# 2_P1.net
KiCad netlist of a schematic drawn in Altium Designer
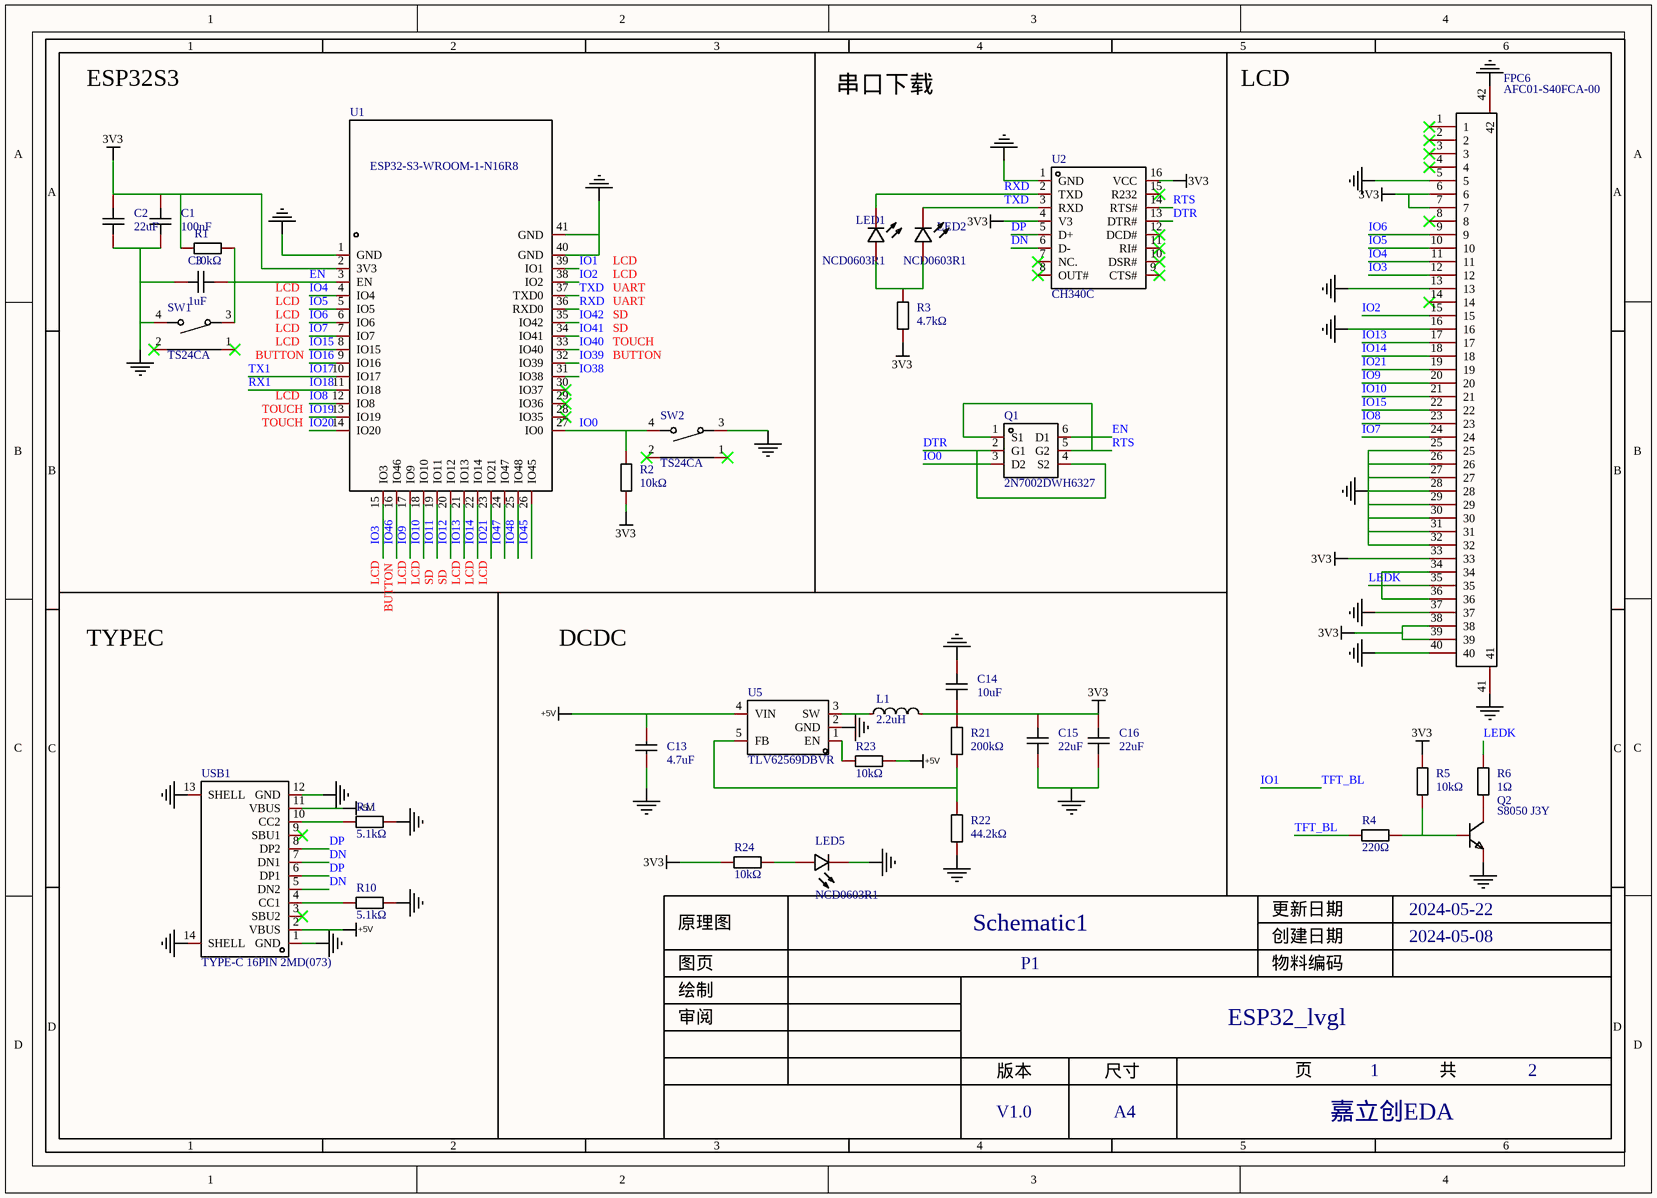
[diagram p0: 2_P1.schdoc]

(export (version "E")
  (design (tool "Eeschema 10.0.6"))
  (components
    (comp (ref "C1")
      (value "100nF")
      (description "容值:100nF;精度:±10%;额定电压:50V;材质(温度系数):X7R;")
      (fields
        (field (name "NAME") "100nF")
        (field (name "MANUFACTURER") "YAGEO(国巨)")
        (field (name "MANUFACTURER PART") "CC0603KRX7R9BB104")
      )
      (libsource (lib "altium-import") (part "root_3_CC0603KRX7R9BB104_"))
    )
    (comp (ref "C2")
      (value "22uF")
      (description "容值:22uF;精度:±20%;额定电压:10V;材质(温度系数):X5R;")
      (fields
        (field (name "NAME") "22uF")
        (field (name "MANUFACTURER") "SAMSUNG(三星)")
        (field (name "MANUFACTURER PART") "CL10A226MP8NUNE")
      )
      (libsource (lib "altium-import") (part "root_1_CL10A226MP8NUNE_"))
    )
    (comp (ref "C3")
      (value "1uF")
      (description "容值:1uF;精度:±10%;额定电压:50V;材质(温度系数):X5R;")
      (fields
        (field (name "NAME") "1uF")
        (field (name "MANUFACTURER") "SAMSUNG(三星)")
        (field (name "MANUFACTURER PART") "CL10A105KB8NNNC")
      )
      (libsource (lib "altium-import") (part "root_2_CL10A105KB8NNNC_"))
    )
    (comp (ref "C13")
      (value "4.7uF")
      (description "容值:4.7uF;精度:±10%;额定电压:25V;材质(温度系数):X5R;")
      (fields
        (field (name "NAME") "4.7uF")
        (field (name "MANUFACTURER") "SAMSUNG(三星)")
        (field (name "MANUFACTURER PART") "CL21A475KAQNNNE")
      )
      (libsource (lib "altium-import") (part "root_1_CL21A475KAQNNNE_"))
    )
    (comp (ref "C14")
      (value "10uF")
      (description "容值:10uF;精度:±20%;额定电压:6.3V;材质(温度系数):X5R;")
      (fields
        (field (name "NAME") "10uF")
        (field (name "MANUFACTURER") "SAMSUNG(三星)")
        (field (name "MANUFACTURER PART") "CL10A106MQ8NNNC")
      )
      (libsource (lib "altium-import") (part "root_1_CL10A106MQ8NNNC_"))
    )
    (comp (ref "C15")
      (value "22uF")
      (description "容值:22uF;精度:±20%;额定电压:6.3V;材质(温度系数):X5R;")
      (fields
        (field (name "NAME") "22uF")
        (field (name "MANUFACTURER") "SAMSUNG(三星)")
        (field (name "MANUFACTURER PART") "CL10A226MQ8NRNC")
      )
      (libsource (lib "altium-import") (part "root_1_CL10A226MQ8NRNC_"))
    )
    (comp (ref "C16")
      (value "22uF")
      (description "容值:22uF;精度:±20%;额定电压:6.3V;材质(温度系数):X5R;")
      (fields
        (field (name "NAME") "22uF")
        (field (name "MANUFACTURER") "SAMSUNG(三星)")
        (field (name "MANUFACTURER PART") "CL10A226MQ8NRNC")
      )
      (libsource (lib "altium-import") (part "root_1_CL10A226MQ8NRNC_"))
    )
    (comp (ref "FPC6")
      (value "AFC01-S40FCA-00")
      (description "锁定特性:翻盖式;触点类型:下接;触点数量:40P;间距:0.5mm;安装类型:卧贴;")
      (fields (field (name "NAME") "AFC01-S40FCA-00") (field (name "MANUFACTURER") "JS(钜硕电子)"))
      (libsource (lib "altium-import") (part "root_0_AFC01-S40FCA-00_"))
    )
    (comp (ref "L1")
      (value "2.2uH")
      (description "电感值:2.2uH;精度:±20%;额定电流:9.5A;饱和电流(Isat):10A;类型:一体成型电感;")
      (fields
        (field (name "NAME") "2.2uH")
        (field (name "MANUFACTURER") "cjiang(长江微电)")
        (field (name "MANUFACTURER PART") "FXL0630-2R2-M")
      )
      (libsource (lib "altium-import") (part "root_0_FXL0630-2R2-M_"))
    )
    (comp (ref "LED1")
      (value "NCD0603R1")
      (fields (field (name "NAME") "NCD0603R1") (field (name "MANUFACTURER") "国星光电"))
      (libsource (lib "altium-import") (part "root_3_NCD0603R1_C84263_"))
    )
    (comp (ref "LED2")
      (value "NCD0603R1")
      (fields (field (name "NAME") "NCD0603R1") (field (name "MANUFACTURER") "国星光电"))
      (libsource (lib "altium-import") (part "root_3_NCD0603R1_C84263_"))
    )
    (comp (ref "LED5")
      (value "NCD0603R1")
      (fields (field (name "NAME") "NCD0603R1") (field (name "MANUFACTURER") "国星光电"))
      (libsource (lib "altium-import") (part "root_2_NCD0603R1_C84263_"))
    )
    (comp (ref "Q1")
      (value "2N7002DWH6327")
      (fields (field (name "NAME") "2N7002DWH6327") (field (name "MANUFACTURER") "Infineon(英飞凌)"))
      (libsource (lib "altium-import") (part "root_0_2N7002DWH6327_"))
    )
    (comp (ref "Q2")
      (value "S8050 J3Y")
      (description "晶体管类型:NPN;集电极电流(Ic):500mA;集射极击穿电压(Vceo):25V;功率(Pd):300mW;直流电流增益(hFE@Ic,Vce):200@50mA,1V;")
      (fields (field (name "NAME") "S8050 J3Y") (field (name "MANUFACTURER") "CJ(江苏长电/长晶)"))
      (libsource (lib "altium-import") (part "root_0_S8050 J3Y_C2146_"))
    )
    (comp (ref "R1")
      (value "10kΩ")
      (description "电阻类型:厚膜电阻;阻值:10kΩ;精度:±1%;功率:100mW;最大工作电压:75V;温度系数:±100ppm/℃;")
      (fields
        (field (name "NAME") "10kΩ")
        (field (name "MANUFACTURER") "UNI-ROYAL(厚声)")
        (field (name "MANUFACTURER PART") "0603WAF1002T5E")
      )
      (libsource (lib "altium-import") (part "root_0_0603WAF1002T5E_"))
    )
    (comp (ref "R2")
      (value "10kΩ")
      (description "电阻类型:厚膜电阻;阻值:10kΩ;精度:±1%;功率:100mW;最大工作电压:75V;温度系数:±100ppm/℃;")
      (fields
        (field (name "NAME") "10kΩ")
        (field (name "MANUFACTURER") "UNI-ROYAL(厚声)")
        (field (name "MANUFACTURER PART") "0603WAF1002T5E")
      )
      (libsource (lib "altium-import") (part "root_1_0603WAF1002T5E_"))
    )
    (comp (ref "R3")
      (value "4.7kΩ")
      (description "电阻类型:厚膜电阻;阻值:4.7kΩ;精度:±1%;功率:100mW;最大工作电压:75V;温度系数:±100ppm/℃;")
      (fields
        (field (name "NAME") "4.7kΩ")
        (field (name "MANUFACTURER") "UNI-ROYAL(厚声)")
        (field (name "MANUFACTURER PART") "0603WAF4701T5E")
      )
      (libsource (lib "altium-import") (part "root_1_0603WAF4701T5E_"))
    )
    (comp (ref "R4")
      (value "220Ω")
      (description "电阻类型:厚膜电阻;阻值:220Ω;精度:±1%;功率:100mW;最大工作电压:75V;温度系数:±100ppm/℃;")
      (fields
        (field (name "NAME") "220Ω")
        (field (name "MANUFACTURER") "UNI-ROYAL(厚声)")
        (field (name "MANUFACTURER PART") "0603WAF2200T5E")
      )
      (libsource (lib "altium-import") (part "root_0_0603WAF2200T5E_"))
    )
    (comp (ref "R5")
      (value "10kΩ")
      (description "电阻类型:厚膜电阻;阻值:10kΩ;精度:±1%;功率:100mW;最大工作电压:75V;温度系数:±100ppm/℃;")
      (fields
        (field (name "NAME") "10kΩ")
        (field (name "MANUFACTURER") "UNI-ROYAL(厚声)")
        (field (name "MANUFACTURER PART") "0603WAF1002T5E")
      )
      (libsource (lib "altium-import") (part "root_1_0603WAF1002T5E_"))
    )
    (comp (ref "R6")
      (value "1Ω")
      (description "电阻类型:厚膜电阻;阻值:1Ω;精度:±1%;功率:100mW;最大工作电压:75V;温度系数:±400ppm/℃;")
      (fields
        (field (name "NAME") "1Ω")
        (field (name "MANUFACTURER") "UNI-ROYAL(厚声)")
        (field (name "MANUFACTURER PART") "0603WAF100KT5E")
      )
      (libsource (lib "altium-import") (part "root_1_0603WAF100KT5E_"))
    )
    (comp (ref "R10")
      (value "5.1kΩ")
      (description "电阻类型:厚膜电阻;阻值:5.1kΩ;精度:±1%;功率:100mW;最大工作电压:75V;温度系数:±100ppm/℃;")
      (fields
        (field (name "NAME") "5.1kΩ")
        (field (name "MANUFACTURER") "UNI-ROYAL(厚声)")
        (field (name "MANUFACTURER PART") "0603WAF5101T5E")
      )
      (libsource (lib "altium-import") (part "root_0_0603WAF5101T5E_"))
    )
    (comp (ref "R11")
      (value "5.1kΩ")
      (description "电阻类型:厚膜电阻;阻值:5.1kΩ;精度:±1%;功率:100mW;最大工作电压:75V;温度系数:±100ppm/℃;")
      (fields
        (field (name "NAME") "5.1kΩ")
        (field (name "MANUFACTURER") "UNI-ROYAL(厚声)")
        (field (name "MANUFACTURER PART") "0603WAF5101T5E")
      )
      (libsource (lib "altium-import") (part "root_0_0603WAF5101T5E_"))
    )
    (comp (ref "R21")
      (value "200kΩ")
      (description "电阻类型:厚膜电阻;阻值:200kΩ;精度:±1%;功率:100mW;最大工作电压:75V;温度系数:±100ppm/℃;")
      (fields
        (field (name "NAME") "200kΩ")
        (field (name "MANUFACTURER") "UNI-ROYAL(厚声)")
        (field (name "MANUFACTURER PART") "0603WAF2003T5E")
      )
      (libsource (lib "altium-import") (part "root_1_0603WAF2003T5E_"))
    )
    (comp (ref "R22")
      (value "44.2kΩ")
      (description "电阻类型:厚膜电阻;阻值:44.2kΩ;精度:±1%;功率:100mW;最大工作电压:75V;温度系数:±100ppm/℃;")
      (fields
        (field (name "NAME") "44.2kΩ")
        (field (name "MANUFACTURER") "UNI-ROYAL(厚声)")
        (field (name "MANUFACTURER PART") "0603WAF4422T5E")
      )
      (libsource (lib "altium-import") (part "root_1_0603WAF4422T5E_"))
    )
    (comp (ref "R23")
      (value "10kΩ")
      (description "电阻类型:厚膜电阻;阻值:10kΩ;精度:±1%;功率:100mW;最大工作电压:75V;温度系数:±100ppm/℃;")
      (fields
        (field (name "NAME") "10kΩ")
        (field (name "MANUFACTURER") "UNI-ROYAL(厚声)")
        (field (name "MANUFACTURER PART") "0603WAF1002T5E")
      )
      (libsource (lib "altium-import") (part "root_0_0603WAF1002T5E_"))
    )
    (comp (ref "R24")
      (value "10kΩ")
      (description "电阻类型:厚膜电阻;阻值:10kΩ;精度:±1%;功率:100mW;最大工作电压:75V;温度系数:±100ppm/℃;")
      (fields
        (field (name "NAME") "10kΩ")
        (field (name "MANUFACTURER") "UNI-ROYAL(厚声)")
        (field (name "MANUFACTURER PART") "0603WAF1002T5E")
      )
      (libsource (lib "altium-import") (part "root_0_0603WAF1002T5E_"))
    )
    (comp (ref "SW1")
      (value "TS24CA")
      (description "电路结构:单刀单掷;按钮形状:矩形按钮;安装方式:卧贴;开关长度:4.55mm;开关宽度:1.8mm;开关高度:3.5mm;触点电流:50mA;额定电压(DC):12V;带灯:-;机械寿命:-;")
      (fields (field (name "NAME") "TS24CA") (field (name "MANUFACTURER") "SHOU HAN(首韩)"))
      (libsource (lib "altium-import") (part "root_2_TS24CA_"))
    )
    (comp (ref "SW2")
      (value "TS24CA")
      (description "电路结构:单刀单掷;按钮形状:矩形按钮;安装方式:卧贴;开关长度:4.55mm;开关宽度:1.8mm;开关高度:3.5mm;触点电流:50mA;额定电压(DC):12V;带灯:-;机械寿命:-;")
      (fields (field (name "NAME") "TS24CA") (field (name "MANUFACTURER") "SHOU HAN(首韩)"))
      (libsource (lib "altium-import") (part "root_2_TS24CA_"))
    )
    (comp (ref "U1")
      (value "ESP32-S3-WROOM-1-N16R8")
      (fields (field (name "NAME") "ESP32-S3-WROOM-1-N16R8") (field (name "MANUFACTURER") "ESPRESSIF(乐鑫)"))
      (libsource (lib "altium-import") (part "root_0_ESP32-S3-WROOM-1-N16R8_"))
    )
    (comp (ref "U2")
      (value "CH340C")
      (description "应用功能:收发器;接口协议:USB 2.0;数据速率:2Mbps;")
      (fields (field (name "NAME") "CH340C") (field (name "MANUFACTURER") "WCH(南京沁恒)"))
      (libsource (lib "altium-import") (part "root_0_CH340C_"))
    )
    (comp (ref "U5")
      (value "TLV62569DBVR")
      (description "功能类型:降压型;输出类型:可调;输入电压:2.5V~5.5V;输出电压:600mV~5.5V;输出电流(最大值):2A;")
      (fields (field (name "NAME") "TLV62569DBVR") (field (name "MANUFACTURER") "TI(德州仪器)"))
      (libsource (lib "altium-import") (part "root_2_TLV62569DBVR_"))
    )
    (comp (ref "USB1")
      (value "TYPE-C 16PIN 2MD(073)")
      (description "连接器类型:Type-C;标准:-;公母:母;端口数量:1;触点数量:16P;安装方式:卧贴;额定电流 - 电源:5A;工作温度范围:-25℃~+85℃;")
      (fields (field (name "NAME") "TYPE-C 16PIN 2MD(073)") (field (name "MANUFACTURER") "SHOU HAN(首韩)"))
      (libsource (lib "altium-import") (part "root_2_TYPE-C 16PIN 2MD(073)_"))
    )
  )
  (nets
    (net (code "1") (name "+5V") (class "Default")
      (node (ref "C13") (pin "2") (pinfunction "2_2") (pintype "passive"))
      (node (ref "R23") (pin "2") (pinfunction "2_2") (pintype "passive"))
      (node (ref "U5") (pin "4") (pinfunction "VIN_4") (pintype "passive"))
      (node (ref "USB1") (pin "11") (pinfunction "VBUS_11") (pintype "passive"))
      (node (ref "USB1") (pin "2") (pinfunction "VBUS_2") (pintype "passive"))
    )
    (net (code "2") (name "/DN") (class "Default")
      (node (ref "U2") (pin "6") (pinfunction "D-_6") (pintype "passive"))
      (node (ref "USB1") (pin "5") (pinfunction "DN2_5") (pintype "passive"))
      (node (ref "USB1") (pin "7") (pinfunction "DN1_7") (pintype "passive"))
    )
    (net (code "3") (name "/DP") (class "Default")
      (node (ref "U2") (pin "5") (pinfunction "D+_5") (pintype "passive"))
      (node (ref "USB1") (pin "6") (pinfunction "DP1_6") (pintype "passive"))
      (node (ref "USB1") (pin "8") (pinfunction "DP2_8") (pintype "passive"))
    )
    (net (code "4") (name "/DTR") (class "Default")
      (node (ref "Q1") (pin "2") (pinfunction "G1_2") (pintype "passive"))
      (node (ref "Q1") (pin "4") (pinfunction "S2_4") (pintype "passive"))
      (node (ref "U2") (pin "13") (pinfunction "DTR#_13") (pintype "passive"))
    )
    (net (code "5") (name "/EN") (class "Default")
      (node (ref "C3") (pin "1") (pinfunction "1_1") (pintype "passive"))
      (node (ref "Q1") (pin "6") (pinfunction "D1_6") (pintype "passive"))
      (node (ref "R1") (pin "2") (pinfunction "2_2") (pintype "passive"))
      (node (ref "SW1") (pin "3") (pinfunction "3_3") (pintype "passive"))
      (node (ref "U1") (pin "3") (pinfunction "EN_3") (pintype "passive"))
    )
    (net (code "6") (name "/IO0") (class "Default")
      (node (ref "Q1") (pin "3") (pinfunction "D2_3") (pintype "passive"))
      (node (ref "R2") (pin "2") (pinfunction "2_2") (pintype "passive"))
      (node (ref "SW2") (pin "4") (pinfunction "4_4") (pintype "passive"))
      (node (ref "U1") (pin "27") (pinfunction "IO0_27") (pintype "passive"))
    )
    (net (code "7") (name "/IO1") (class "Default")
      (node (ref "R4") (pin "1") (pinfunction "1_1") (pintype "passive"))
      (node (ref "U1") (pin "39") (pinfunction "IO1_39") (pintype "passive"))
    )
    (net (code "8") (name "/IO2") (class "Default")
      (node (ref "FPC6") (pin "15") (pinfunction "15_15") (pintype "passive"))
      (node (ref "U1") (pin "38") (pinfunction "IO2_38") (pintype "passive"))
    )
    (net (code "9") (name "/IO3") (class "Default")
      (node (ref "FPC6") (pin "12") (pinfunction "12_12") (pintype "passive"))
      (node (ref "U1") (pin "15") (pinfunction "IO3_15") (pintype "passive"))
    )
    (net (code "10") (name "/IO4") (class "Default")
      (node (ref "FPC6") (pin "11") (pinfunction "11_11") (pintype "passive"))
      (node (ref "U1") (pin "4") (pinfunction "IO4_4") (pintype "passive"))
    )
    (net (code "11") (name "/IO5") (class "Default")
      (node (ref "FPC6") (pin "10") (pinfunction "10_10") (pintype "passive"))
      (node (ref "U1") (pin "5") (pinfunction "IO5_5") (pintype "passive"))
    )
    (net (code "12") (name "/IO6") (class "Default")
      (node (ref "FPC6") (pin "9") (pinfunction "9_9") (pintype "passive"))
      (node (ref "U1") (pin "6") (pinfunction "IO6_6") (pintype "passive"))
    )
    (net (code "13") (name "/IO7") (class "Default")
      (node (ref "FPC6") (pin "24") (pinfunction "24_24") (pintype "passive"))
      (node (ref "U1") (pin "7") (pinfunction "IO7_7") (pintype "passive"))
    )
    (net (code "14") (name "/IO8") (class "Default")
      (node (ref "FPC6") (pin "23") (pinfunction "23_23") (pintype "passive"))
      (node (ref "U1") (pin "12") (pinfunction "IO8_12") (pintype "passive"))
    )
    (net (code "15") (name "/IO9") (class "Default")
      (node (ref "FPC6") (pin "20") (pinfunction "20_20") (pintype "passive"))
      (node (ref "U1") (pin "17") (pinfunction "IO9_17") (pintype "passive"))
    )
    (net (code "16") (name "/IO10") (class "Default")
      (node (ref "FPC6") (pin "21") (pinfunction "21_21") (pintype "passive"))
      (node (ref "U1") (pin "18") (pinfunction "IO10_18") (pintype "passive"))
    )
    (net (code "17") (name "/IO11") (class "Default")
      (node (ref "U1") (pin "19") (pinfunction "IO11_19") (pintype "passive"))
    )
    (net (code "18") (name "/IO12") (class "Default")
      (node (ref "U1") (pin "20") (pinfunction "IO12_20") (pintype "passive"))
    )
    (net (code "19") (name "/IO13") (class "Default")
      (node (ref "FPC6") (pin "17") (pinfunction "17_17") (pintype "passive"))
      (node (ref "U1") (pin "21") (pinfunction "IO13_21") (pintype "passive"))
    )
    (net (code "20") (name "/IO14") (class "Default")
      (node (ref "FPC6") (pin "18") (pinfunction "18_18") (pintype "passive"))
      (node (ref "U1") (pin "22") (pinfunction "IO14_22") (pintype "passive"))
    )
    (net (code "21") (name "/IO15") (class "Default")
      (node (ref "FPC6") (pin "22") (pinfunction "22_22") (pintype "passive"))
      (node (ref "U1") (pin "8") (pinfunction "IO15_8") (pintype "passive"))
    )
    (net (code "22") (name "/IO16") (class "Default")
      (node (ref "U1") (pin "9") (pinfunction "IO16_9") (pintype "passive"))
    )
    (net (code "23") (name "/IO17") (class "Default")
      (node (ref "U1") (pin "10") (pinfunction "IO17_10") (pintype "passive"))
    )
    (net (code "24") (name "/IO18") (class "Default")
      (node (ref "U1") (pin "11") (pinfunction "IO18_11") (pintype "passive"))
    )
    (net (code "25") (name "/IO19") (class "Default")
      (node (ref "U1") (pin "13") (pinfunction "IO19_13") (pintype "passive"))
    )
    (net (code "26") (name "/IO20") (class "Default")
      (node (ref "U1") (pin "14") (pinfunction "IO20_14") (pintype "passive"))
    )
    (net (code "27") (name "/IO21") (class "Default")
      (node (ref "FPC6") (pin "19") (pinfunction "19_19") (pintype "passive"))
      (node (ref "U1") (pin "23") (pinfunction "IO21_23") (pintype "passive"))
    )
    (net (code "28") (name "/IO38") (class "Default")
      (node (ref "U1") (pin "31") (pinfunction "IO38_31") (pintype "passive"))
    )
    (net (code "29") (name "/IO39") (class "Default")
      (node (ref "U1") (pin "32") (pinfunction "IO39_32") (pintype "passive"))
    )
    (net (code "30") (name "/IO40") (class "Default")
      (node (ref "U1") (pin "33") (pinfunction "IO40_33") (pintype "passive"))
    )
    (net (code "31") (name "/IO41") (class "Default")
      (node (ref "U1") (pin "34") (pinfunction "IO41_34") (pintype "passive"))
    )
    (net (code "32") (name "/IO42") (class "Default")
      (node (ref "U1") (pin "35") (pinfunction "IO42_35") (pintype "passive"))
    )
    (net (code "33") (name "/IO45") (class "Default")
      (node (ref "U1") (pin "26") (pinfunction "IO45_26") (pintype "passive"))
    )
    (net (code "34") (name "/IO46") (class "Default")
      (node (ref "U1") (pin "16") (pinfunction "IO46_16") (pintype "passive"))
    )
    (net (code "35") (name "/IO47") (class "Default")
      (node (ref "U1") (pin "24") (pinfunction "IO47_24") (pintype "passive"))
    )
    (net (code "36") (name "/IO48") (class "Default")
      (node (ref "U1") (pin "25") (pinfunction "IO48_25") (pintype "passive"))
    )
    (net (code "37") (name "/LEDK") (class "Default")
      (node (ref "FPC6") (pin "34") (pinfunction "34_34") (pintype "passive"))
      (node (ref "FPC6") (pin "35") (pinfunction "35_35") (pintype "passive"))
      (node (ref "FPC6") (pin "36") (pinfunction "36_36") (pintype "passive"))
      (node (ref "R6") (pin "2") (pinfunction "2_2") (pintype "passive"))
    )
    (net (code "38") (name "/RTS") (class "Default")
      (node (ref "Q1") (pin "1") (pinfunction "S1_1") (pintype "passive"))
      (node (ref "Q1") (pin "5") (pinfunction "G2_5") (pintype "passive"))
      (node (ref "U2") (pin "14") (pinfunction "RTS#_14") (pintype "passive"))
    )
    (net (code "39") (name "/RXD") (class "Default")
      (node (ref "LED1") (pin "1") (pinfunction "K_1") (pintype "passive"))
      (node (ref "U1") (pin "36") (pinfunction "RXD0_36") (pintype "passive"))
      (node (ref "U2") (pin "2") (pinfunction "TXD_2") (pintype "passive"))
    )
    (net (code "40") (name "/TXD") (class "Default")
      (node (ref "LED2") (pin "1") (pinfunction "K_1") (pintype "passive"))
      (node (ref "U1") (pin "37") (pinfunction "TXD0_37") (pintype "passive"))
      (node (ref "U2") (pin "3") (pinfunction "RXD_3") (pintype "passive"))
    )
    (net (code "41") (name "3V3") (class "Default")
      (node (ref "C1") (pin "1") (pinfunction "1_1") (pintype "passive"))
      (node (ref "C14") (pin "1") (pinfunction "1_1") (pintype "passive"))
      (node (ref "C15") (pin "2") (pinfunction "2_2") (pintype "passive"))
      (node (ref "C16") (pin "2") (pinfunction "2_2") (pintype "passive"))
      (node (ref "C2") (pin "2") (pinfunction "2_2") (pintype "passive"))
      (node (ref "FPC6") (pin "33") (pinfunction "33_33") (pintype "passive"))
      (node (ref "FPC6") (pin "38") (pinfunction "38_38") (pintype "passive"))
      (node (ref "FPC6") (pin "39") (pinfunction "39_39") (pintype "passive"))
      (node (ref "FPC6") (pin "6") (pinfunction "6_6") (pintype "passive"))
      (node (ref "FPC6") (pin "7") (pinfunction "7_7") (pintype "passive"))
      (node (ref "L1") (pin "2") (pinfunction "2_2") (pintype "passive"))
      (node (ref "R1") (pin "1") (pinfunction "1_1") (pintype "passive"))
      (node (ref "R2") (pin "1") (pinfunction "1_1") (pintype "passive"))
      (node (ref "R21") (pin "2") (pinfunction "2_2") (pintype "passive"))
      (node (ref "R24") (pin "1") (pinfunction "1_1") (pintype "passive"))
      (node (ref "R3") (pin "1") (pinfunction "1_1") (pintype "passive"))
      (node (ref "R5") (pin "2") (pinfunction "2_2") (pintype "passive"))
      (node (ref "U1") (pin "2") (pinfunction "3V3_2") (pintype "passive"))
      (node (ref "U2") (pin "16") (pinfunction "VCC_16") (pintype "passive"))
      (node (ref "U2") (pin "4") (pinfunction "V3_4") (pintype "passive"))
    )
    (net (code "42") (name "<NO NET>") (class "Default")
      (node (ref "C1") (pin "2") (pinfunction "2_2") (pintype "passive"))
      (node (ref "C13") (pin "1") (pinfunction "1_1") (pintype "passive"))
      (node (ref "C14") (pin "2") (pinfunction "2_2") (pintype "passive"))
      (node (ref "C15") (pin "1") (pinfunction "1_1") (pintype "passive"))
      (node (ref "C16") (pin "1") (pinfunction "1_1") (pintype "passive"))
      (node (ref "C2") (pin "1") (pinfunction "1_1") (pintype "passive"))
      (node (ref "C3") (pin "2") (pinfunction "2_2") (pintype "passive"))
      (node (ref "FPC6") (pin "13") (pinfunction "13_13") (pintype "passive"))
      (node (ref "FPC6") (pin "16") (pinfunction "16_16") (pintype "passive"))
      (node (ref "FPC6") (pin "25") (pinfunction "25_25") (pintype "passive"))
      (node (ref "FPC6") (pin "26") (pinfunction "26_26") (pintype "passive"))
      (node (ref "FPC6") (pin "27") (pinfunction "27_27") (pintype "passive"))
      (node (ref "FPC6") (pin "28") (pinfunction "28_28") (pintype "passive"))
      (node (ref "FPC6") (pin "29") (pinfunction "29_29") (pintype "passive"))
      (node (ref "FPC6") (pin "30") (pinfunction "30_30") (pintype "passive"))
      (node (ref "FPC6") (pin "31") (pinfunction "31_31") (pintype "passive"))
      (node (ref "FPC6") (pin "32") (pinfunction "32_32") (pintype "passive"))
      (node (ref "FPC6") (pin "37") (pinfunction "37_37") (pintype "passive"))
      (node (ref "FPC6") (pin "40") (pinfunction "40_40") (pintype "passive"))
      (node (ref "FPC6") (pin "41") (pinfunction "41_41") (pintype "passive"))
      (node (ref "FPC6") (pin "42") (pinfunction "42_42") (pintype "passive"))
      (node (ref "FPC6") (pin "5") (pinfunction "5_5") (pintype "passive"))
      (node (ref "LED5") (pin "1") (pinfunction "K_1") (pintype "passive"))
      (node (ref "Q2") (pin "2") (pinfunction "E_2") (pintype "passive"))
      (node (ref "R10") (pin "2") (pinfunction "2_2") (pintype "passive"))
      (node (ref "R11") (pin "2") (pinfunction "2_2") (pintype "passive"))
      (node (ref "R22") (pin "1") (pinfunction "1_1") (pintype "passive"))
      (node (ref "SW1") (pin "4") (pinfunction "4_4") (pintype "passive"))
      (node (ref "SW2") (pin "3") (pinfunction "3_3") (pintype "passive"))
      (node (ref "U1") (pin "1") (pinfunction "GND_1") (pintype "passive"))
      (node (ref "U1") (pin "40") (pinfunction "GND_40") (pintype "passive"))
      (node (ref "U1") (pin "41") (pinfunction "GND_41") (pintype "passive"))
      (node (ref "U2") (pin "1") (pinfunction "GND_1") (pintype "passive"))
      (node (ref "U5") (pin "2") (pinfunction "GND_2") (pintype "passive"))
      (node (ref "USB1") (pin "1") (pinfunction "GND_1") (pintype "passive"))
      (node (ref "USB1") (pin "12") (pinfunction "GND_12") (pintype "passive"))
      (node (ref "USB1") (pin "13") (pinfunction "SHELL_13") (pintype "passive"))
      (node (ref "USB1") (pin "14") (pinfunction "SHELL_14") (pintype "passive"))
    )
    (net (code "43") (name "Net-(LED1-A)") (class "Default")
      (node (ref "LED1") (pin "2") (pinfunction "A_2") (pintype "passive"))
      (node (ref "LED2") (pin "2") (pinfunction "A_2") (pintype "passive"))
      (node (ref "R3") (pin "2") (pinfunction "2_2") (pintype "passive"))
    )
    (net (code "44") (name "Net-(LED5-A)") (class "Default")
      (node (ref "LED5") (pin "2") (pinfunction "A_2") (pintype "passive"))
      (node (ref "R24") (pin "2") (pinfunction "2_2") (pintype "passive"))
    )
    (net (code "45") (name "Net-(Q2-B)") (class "Default")
      (node (ref "Q2") (pin "1") (pinfunction "B_1") (pintype "passive"))
      (node (ref "R4") (pin "2") (pinfunction "2_2") (pintype "passive"))
      (node (ref "R5") (pin "1") (pinfunction "1_1") (pintype "passive"))
    )
    (net (code "46") (name "Net-(Q2-C)") (class "Default")
      (node (ref "Q2") (pin "3") (pinfunction "C_3") (pintype "passive"))
      (node (ref "R6") (pin "1") (pinfunction "1_1") (pintype "passive"))
    )
    (net (code "47") (name "Net-(U5-EN)") (class "Default")
      (node (ref "R23") (pin "1") (pinfunction "1_1") (pintype "passive"))
      (node (ref "U5") (pin "1") (pinfunction "EN_1") (pintype "passive"))
    )
    (net (code "48") (name "Net-(U5-FB)") (class "Default")
      (node (ref "R21") (pin "1") (pinfunction "1_1") (pintype "passive"))
      (node (ref "R22") (pin "2") (pinfunction "2_2") (pintype "passive"))
      (node (ref "U5") (pin "5") (pinfunction "FB_5") (pintype "passive"))
    )
    (net (code "49") (name "Net-(U5-SW)") (class "Default")
      (node (ref "L1") (pin "1") (pinfunction "1_1") (pintype "passive"))
      (node (ref "U5") (pin "3") (pinfunction "SW_3") (pintype "passive"))
    )
    (net (code "50") (name "Net-(USB1-CC1)") (class "Default")
      (node (ref "R10") (pin "1") (pinfunction "1_1") (pintype "passive"))
      (node (ref "USB1") (pin "4") (pinfunction "CC1_4") (pintype "passive"))
    )
    (net (code "51") (name "Net-(USB1-CC2)") (class "Default")
      (node (ref "R11") (pin "1") (pinfunction "1_1") (pintype "passive"))
      (node (ref "USB1") (pin "10") (pinfunction "CC2_10") (pintype "passive"))
    )
    (net (code "52") (name "unconnected-(FPC6-Pad1)") (class "Default")
      (node (ref "FPC6") (pin "1") (pinfunction "1_1") (pintype "passive+no_connect"))
    )
    (net (code "53") (name "unconnected-(FPC6-Pad2)") (class "Default")
      (node (ref "FPC6") (pin "2") (pinfunction "2_2") (pintype "passive+no_connect"))
    )
    (net (code "54") (name "unconnected-(FPC6-Pad3)") (class "Default")
      (node (ref "FPC6") (pin "3") (pinfunction "3_3") (pintype "passive+no_connect"))
    )
    (net (code "55") (name "unconnected-(FPC6-Pad4)") (class "Default")
      (node (ref "FPC6") (pin "4") (pinfunction "4_4") (pintype "passive+no_connect"))
    )
    (net (code "56") (name "unconnected-(FPC6-Pad8)") (class "Default")
      (node (ref "FPC6") (pin "8") (pinfunction "8_8") (pintype "passive+no_connect"))
    )
    (net (code "57") (name "unconnected-(FPC6-Pad14)") (class "Default")
      (node (ref "FPC6") (pin "14") (pinfunction "14_14") (pintype "passive+no_connect"))
    )
    (net (code "58") (name "unconnected-(SW1-Pad1)") (class "Default")
      (node (ref "SW1") (pin "1") (pinfunction "1_1") (pintype "passive+no_connect"))
    )
    (net (code "59") (name "unconnected-(SW1-Pad2)") (class "Default")
      (node (ref "SW1") (pin "2") (pinfunction "2_2") (pintype "passive+no_connect"))
    )
    (net (code "60") (name "unconnected-(SW2-Pad1)") (class "Default")
      (node (ref "SW2") (pin "1") (pinfunction "1_1") (pintype "passive+no_connect"))
    )
    (net (code "61") (name "unconnected-(SW2-Pad2)") (class "Default")
      (node (ref "SW2") (pin "2") (pinfunction "2_2") (pintype "passive+no_connect"))
    )
    (net (code "62") (name "unconnected-(U1-IO35-Pad28)") (class "Default")
      (node (ref "U1") (pin "28") (pinfunction "IO35_28") (pintype "passive+no_connect"))
    )
    (net (code "63") (name "unconnected-(U1-IO36-Pad29)") (class "Default")
      (node (ref "U1") (pin "29") (pinfunction "IO36_29") (pintype "passive+no_connect"))
    )
    (net (code "64") (name "unconnected-(U1-IO37-Pad30)") (class "Default")
      (node (ref "U1") (pin "30") (pinfunction "IO37_30") (pintype "passive+no_connect"))
    )
    (net (code "65") (name "unconnected-(U2-CTS#-Pad9)") (class "Default")
      (node (ref "U2") (pin "9") (pinfunction "CTS#_9") (pintype "passive+no_connect"))
    )
    (net (code "66") (name "unconnected-(U2-DCD#-Pad12)") (class "Default")
      (node (ref "U2") (pin "12") (pinfunction "DCD#_12") (pintype "passive+no_connect"))
    )
    (net (code "67") (name "unconnected-(U2-DSR#-Pad10)") (class "Default")
      (node (ref "U2") (pin "10") (pinfunction "DSR#_10") (pintype "passive+no_connect"))
    )
    (net (code "68") (name "unconnected-(U2-NC.-Pad7)") (class "Default")
      (node (ref "U2") (pin "7") (pinfunction "NC._7") (pintype "passive+no_connect"))
    )
    (net (code "69") (name "unconnected-(U2-OUT#-Pad8)") (class "Default")
      (node (ref "U2") (pin "8") (pinfunction "OUT#_8") (pintype "passive+no_connect"))
    )
    (net (code "70") (name "unconnected-(U2-R232-Pad15)") (class "Default")
      (node (ref "U2") (pin "15") (pinfunction "R232_15") (pintype "passive+no_connect"))
    )
    (net (code "71") (name "unconnected-(U2-RI#-Pad11)") (class "Default")
      (node (ref "U2") (pin "11") (pinfunction "RI#_11") (pintype "passive+no_connect"))
    )
    (net (code "72") (name "unconnected-(USB1-SBU1-Pad9)") (class "Default")
      (node (ref "USB1") (pin "9") (pinfunction "SBU1_9") (pintype "passive+no_connect"))
    )
    (net (code "73") (name "unconnected-(USB1-SBU2-Pad3)") (class "Default")
      (node (ref "USB1") (pin "3") (pinfunction "SBU2_3") (pintype "passive+no_connect"))
    )
  )
)
